# bot_schem_rev9.net
KiCad netlist of a schematic drawn in Altium Designer
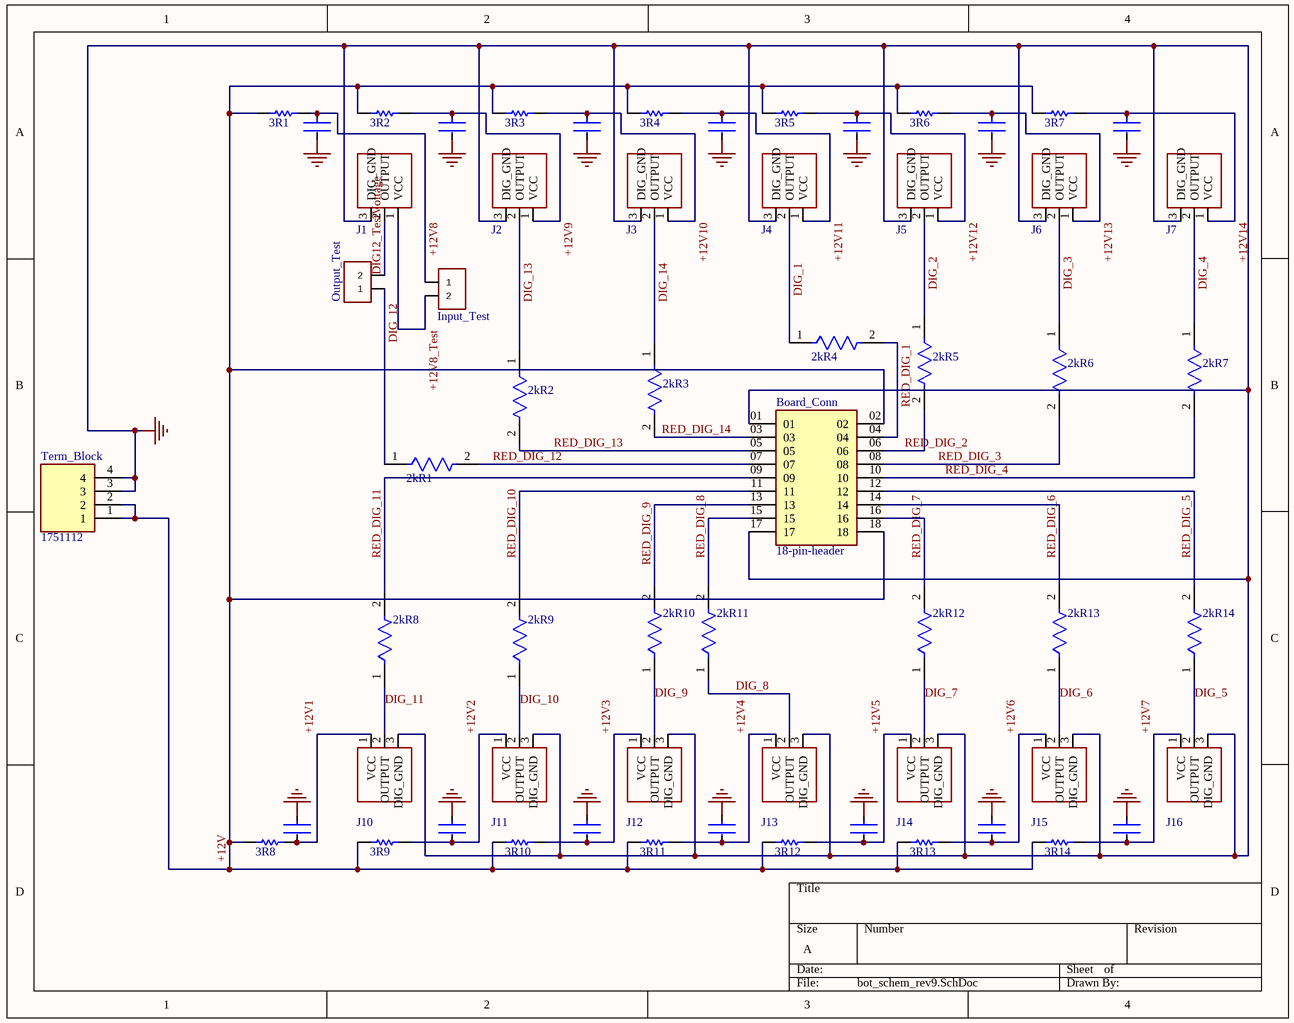
[diagram p0: bot_schem_rev9.SchDoc]

(export (version "E")
  (design (tool "Eeschema 10.0.6"))
  (components
    (comp (ref "2kR1")
      (value "CRCW06031K80FKEA")
      (footprint "2kOhm")
      (description "Res Thick Film 0603 1.8K Ohm 1% 1/10W ±100ppm/°C Molded SMD Paper T/R")
      (fields (field (name "MANUFACTURER") "Vishay") (field (name "TOLERANCE") "1%"))
      (libsource (lib "ps_schlib") (part "CRCW06031K80FKEA"))
    )
    (comp (ref "2kR2")
      (value "CRCW06031K80FKEA")
      (footprint "2kOhm")
      (description "Res Thick Film 0603 1.8K Ohm 1% 1/10W ±100ppm/°C Molded SMD Paper T/R")
      (fields (field (name "MANUFACTURER") "Vishay") (field (name "TOLERANCE") "1%"))
      (libsource (lib "ps_schlib") (part "CRCW06031K80FKEA"))
    )
    (comp (ref "2kR3")
      (value "CRCW06031K80FKEA")
      (footprint "2kOhm")
      (description "Res Thick Film 0603 1.8K Ohm 1% 1/10W ±100ppm/°C Molded SMD Paper T/R")
      (fields (field (name "MANUFACTURER") "Vishay") (field (name "TOLERANCE") "1%"))
      (libsource (lib "ps_schlib") (part "CRCW06031K80FKEA"))
    )
    (comp (ref "2kR4")
      (value "CRCW06031K80FKEA")
      (footprint "2kOhm")
      (description "Res Thick Film 0603 1.8K Ohm 1% 1/10W ±100ppm/°C Molded SMD Paper T/R")
      (fields (field (name "MANUFACTURER") "Vishay") (field (name "TOLERANCE") "1%"))
      (libsource (lib "ps_schlib") (part "CRCW06031K80FKEA"))
    )
    (comp (ref "2kR5")
      (value "CRCW06031K80FKEA")
      (footprint "2kOhm")
      (description "Res Thick Film 0603 1.8K Ohm 1% 1/10W ±100ppm/°C Molded SMD Paper T/R")
      (fields (field (name "MANUFACTURER") "Vishay") (field (name "TOLERANCE") "1%"))
      (libsource (lib "ps_schlib") (part "CRCW06031K80FKEA"))
    )
    (comp (ref "2kR6")
      (value "CRCW06031K80FKEA")
      (footprint "2kOhm")
      (description "Res Thick Film 0603 1.8K Ohm 1% 1/10W ±100ppm/°C Molded SMD Paper T/R")
      (fields (field (name "MANUFACTURER") "Vishay") (field (name "TOLERANCE") "1%"))
      (libsource (lib "ps_schlib") (part "CRCW06031K80FKEA"))
    )
    (comp (ref "2kR7")
      (value "CRCW06031K80FKEA")
      (footprint "2kOhm")
      (description "Res Thick Film 0603 1.8K Ohm 1% 1/10W ±100ppm/°C Molded SMD Paper T/R")
      (fields (field (name "MANUFACTURER") "Vishay") (field (name "TOLERANCE") "1%"))
      (libsource (lib "ps_schlib") (part "CRCW06031K80FKEA"))
    )
    (comp (ref "2kR8")
      (value "CRCW06031K80FKEA")
      (footprint "2kOhm")
      (description "Res Thick Film 0603 1.8K Ohm 1% 1/10W ±100ppm/°C Molded SMD Paper T/R")
      (fields (field (name "MANUFACTURER") "Vishay") (field (name "TOLERANCE") "1%"))
      (libsource (lib "ps_schlib") (part "CRCW06031K80FKEA"))
    )
    (comp (ref "2kR9")
      (value "CRCW06031K80FKEA")
      (footprint "2kOhm")
      (description "Res Thick Film 0603 1.8K Ohm 1% 1/10W ±100ppm/°C Molded SMD Paper T/R")
      (fields (field (name "MANUFACTURER") "Vishay") (field (name "TOLERANCE") "1%"))
      (libsource (lib "ps_schlib") (part "CRCW06031K80FKEA"))
    )
    (comp (ref "2kR10")
      (value "CRCW06031K80FKEA")
      (footprint "2kOhm")
      (description "Res Thick Film 0603 1.8K Ohm 1% 1/10W ±100ppm/°C Molded SMD Paper T/R")
      (fields (field (name "MANUFACTURER") "Vishay") (field (name "TOLERANCE") "1%"))
      (libsource (lib "ps_schlib") (part "CRCW06031K80FKEA"))
    )
    (comp (ref "2kR11")
      (value "CRCW06031K80FKEA")
      (footprint "2kOhm")
      (description "Res Thick Film 0603 1.8K Ohm 1% 1/10W ±100ppm/°C Molded SMD Paper T/R")
      (fields (field (name "MANUFACTURER") "Vishay") (field (name "TOLERANCE") "1%"))
      (libsource (lib "ps_schlib") (part "CRCW06031K80FKEA"))
    )
    (comp (ref "2kR12")
      (value "CRCW06031K80FKEA")
      (footprint "2kOhm")
      (description "Res Thick Film 0603 1.8K Ohm 1% 1/10W ±100ppm/°C Molded SMD Paper T/R")
      (fields (field (name "MANUFACTURER") "Vishay") (field (name "TOLERANCE") "1%"))
      (libsource (lib "ps_schlib") (part "CRCW06031K80FKEA"))
    )
    (comp (ref "2kR13")
      (value "CRCW06031K80FKEA")
      (footprint "2kOhm")
      (description "Res Thick Film 0603 1.8K Ohm 1% 1/10W ±100ppm/°C Molded SMD Paper T/R")
      (fields (field (name "MANUFACTURER") "Vishay") (field (name "TOLERANCE") "1%"))
      (libsource (lib "ps_schlib") (part "CRCW06031K80FKEA"))
    )
    (comp (ref "2kR14")
      (value "CRCW06031K80FKEA")
      (footprint "2kOhm")
      (description "Res Thick Film 0603 1.8K Ohm 1% 1/10W ±100ppm/°C Molded SMD Paper T/R")
      (fields (field (name "MANUFACTURER") "Vishay") (field (name "TOLERANCE") "1%"))
      (libsource (lib "ps_schlib") (part "CRCW06031K80FKEA"))
    )
    (comp (ref "3R1")
      (value "ERJ-2BQJR30X")
      (footprint "03 Ohm")
      (description "RES 0.3 OHM 5% 1/6W 0402")
      (fields (field (name "MANUFACTURER") "Panasonic") (field (name "TOLERANCE") "5%"))
      (libsource (lib "ps_schlib") (part "ERJ-2BQJR30X"))
    )
    (comp (ref "3R2")
      (value "ERJ-2BQJR30X")
      (footprint "03 Ohm")
      (description "RES 0.3 OHM 5% 1/6W 0402")
      (fields (field (name "MANUFACTURER") "Panasonic") (field (name "TOLERANCE") "5%"))
      (libsource (lib "ps_schlib") (part "ERJ-2BQJR30X"))
    )
    (comp (ref "3R3")
      (value "ERJ-2BQJR30X")
      (footprint "03 Ohm")
      (description "RES 0.3 OHM 5% 1/6W 0402")
      (fields (field (name "MANUFACTURER") "Panasonic") (field (name "TOLERANCE") "5%"))
      (libsource (lib "ps_schlib") (part "ERJ-2BQJR30X"))
    )
    (comp (ref "3R4")
      (value "ERJ-2BQJR30X")
      (footprint "03 Ohm")
      (description "RES 0.3 OHM 5% 1/6W 0402")
      (fields (field (name "MANUFACTURER") "Panasonic") (field (name "TOLERANCE") "5%"))
      (libsource (lib "ps_schlib") (part "ERJ-2BQJR30X"))
    )
    (comp (ref "3R5")
      (value "ERJ-2BQJR30X")
      (footprint "03 Ohm")
      (description "RES 0.3 OHM 5% 1/6W 0402")
      (fields (field (name "MANUFACTURER") "Panasonic") (field (name "TOLERANCE") "5%"))
      (libsource (lib "ps_schlib") (part "ERJ-2BQJR30X"))
    )
    (comp (ref "3R6")
      (value "ERJ-2BQJR30X")
      (footprint "03 Ohm")
      (description "RES 0.3 OHM 5% 1/6W 0402")
      (fields (field (name "MANUFACTURER") "Panasonic") (field (name "TOLERANCE") "5%"))
      (libsource (lib "ps_schlib") (part "ERJ-2BQJR30X"))
    )
    (comp (ref "3R7")
      (value "ERJ-2BQJR30X")
      (footprint "03 Ohm")
      (description "RES 0.3 OHM 5% 1/6W 0402")
      (fields (field (name "MANUFACTURER") "Panasonic") (field (name "TOLERANCE") "5%"))
      (libsource (lib "ps_schlib") (part "ERJ-2BQJR30X"))
    )
    (comp (ref "3R8")
      (value "ERJ-2BQJR30X")
      (footprint "03 Ohm")
      (description "RES 0.3 OHM 5% 1/6W 0402")
      (fields (field (name "MANUFACTURER") "Panasonic") (field (name "TOLERANCE") "5%"))
      (libsource (lib "ps_schlib") (part "ERJ-2BQJR30X"))
    )
    (comp (ref "3R9")
      (value "ERJ-2BQJR30X")
      (footprint "03 Ohm")
      (description "RES 0.3 OHM 5% 1/6W 0402")
      (fields (field (name "MANUFACTURER") "Panasonic") (field (name "TOLERANCE") "5%"))
      (libsource (lib "ps_schlib") (part "ERJ-2BQJR30X"))
    )
    (comp (ref "3R10")
      (value "ERJ-2BQJR30X")
      (footprint "03 Ohm")
      (description "RES 0.3 OHM 5% 1/6W 0402")
      (fields (field (name "MANUFACTURER") "Panasonic") (field (name "TOLERANCE") "5%"))
      (libsource (lib "ps_schlib") (part "ERJ-2BQJR30X"))
    )
    (comp (ref "3R11")
      (value "ERJ-2BQJR30X")
      (footprint "03 Ohm")
      (description "RES 0.3 OHM 5% 1/6W 0402")
      (fields (field (name "MANUFACTURER") "Panasonic") (field (name "TOLERANCE") "5%"))
      (libsource (lib "ps_schlib") (part "ERJ-2BQJR30X"))
    )
    (comp (ref "3R12")
      (value "ERJ-2BQJR30X")
      (footprint "03 Ohm")
      (description "RES 0.3 OHM 5% 1/6W 0402")
      (fields (field (name "MANUFACTURER") "Panasonic") (field (name "TOLERANCE") "5%"))
      (libsource (lib "ps_schlib") (part "ERJ-2BQJR30X"))
    )
    (comp (ref "3R13")
      (value "ERJ-2BQJR30X")
      (footprint "03 Ohm")
      (description "RES 0.3 OHM 5% 1/6W 0402")
      (fields (field (name "MANUFACTURER") "Panasonic") (field (name "TOLERANCE") "5%"))
      (libsource (lib "ps_schlib") (part "ERJ-2BQJR30X"))
    )
    (comp (ref "3R14")
      (value "ERJ-2BQJR30X")
      (footprint "03 Ohm")
      (description "RES 0.3 OHM 5% 1/6W 0402")
      (fields (field (name "MANUFACTURER") "Panasonic") (field (name "TOLERANCE") "5%"))
      (libsource (lib "ps_schlib") (part "ERJ-2BQJR30X"))
    )
    (comp (ref "Board_Conn")
      (value "18-pin-header")
      (footprint "18 pin header")
      (libsource (lib "bot_schlib") (part "18-pin-header"))
    )
    (comp (ref "C1")
      (value "C0805C104K5RACTU")
      (footprint "100nF")
      (description "Cap Ceramic 0.1uF 50V X7R 10% SMD 2.0 x 1.2 mm 125 C Paper T/R")
      (fields (field (name "MANUFACTURER") "KEMET") (field (name "TOLERANCE") "10%"))
      (libsource (lib "ps_schlib") (part "C0805C104K5RACTU"))
    )
    (comp (ref "C2")
      (value "C0805C104K5RACTU")
      (footprint "100nF")
      (description "Cap Ceramic 0.1uF 50V X7R 10% SMD 2.0 x 1.2 mm 125 C Paper T/R")
      (fields (field (name "MANUFACTURER") "KEMET") (field (name "TOLERANCE") "10%"))
      (libsource (lib "ps_schlib") (part "C0805C104K5RACTU"))
    )
    (comp (ref "C3")
      (value "C0805C104K5RACTU")
      (footprint "100nF")
      (description "Cap Ceramic 0.1uF 50V X7R 10% SMD 2.0 x 1.2 mm 125 C Paper T/R")
      (fields (field (name "MANUFACTURER") "KEMET") (field (name "TOLERANCE") "10%"))
      (libsource (lib "ps_schlib") (part "C0805C104K5RACTU"))
    )
    (comp (ref "C4")
      (value "C0805C104K5RACTU")
      (footprint "100nF")
      (description "Cap Ceramic 0.1uF 50V X7R 10% SMD 2.0 x 1.2 mm 125 C Paper T/R")
      (fields (field (name "MANUFACTURER") "KEMET") (field (name "TOLERANCE") "10%"))
      (libsource (lib "ps_schlib") (part "C0805C104K5RACTU"))
    )
    (comp (ref "C5")
      (value "C0805C104K5RACTU")
      (footprint "100nF")
      (description "Cap Ceramic 0.1uF 50V X7R 10% SMD 2.0 x 1.2 mm 125 C Paper T/R")
      (fields (field (name "MANUFACTURER") "KEMET") (field (name "TOLERANCE") "10%"))
      (libsource (lib "ps_schlib") (part "C0805C104K5RACTU"))
    )
    (comp (ref "C6")
      (value "C0805C104K5RACTU")
      (footprint "100nF")
      (description "Cap Ceramic 0.1uF 50V X7R 10% SMD 2.0 x 1.2 mm 125 C Paper T/R")
      (fields (field (name "MANUFACTURER") "KEMET") (field (name "TOLERANCE") "10%"))
      (libsource (lib "ps_schlib") (part "C0805C104K5RACTU"))
    )
    (comp (ref "C7")
      (value "C0805C104K5RACTU")
      (footprint "100nF")
      (description "Cap Ceramic 0.1uF 50V X7R 10% SMD 2.0 x 1.2 mm 125 C Paper T/R")
      (fields (field (name "MANUFACTURER") "KEMET") (field (name "TOLERANCE") "10%"))
      (libsource (lib "ps_schlib") (part "C0805C104K5RACTU"))
    )
    (comp (ref "C8")
      (value "C0805C104K5RACTU")
      (footprint "100nF")
      (description "Cap Ceramic 0.1uF 50V X7R 10% SMD 2.0 x 1.2 mm 125 C Paper T/R")
      (fields (field (name "MANUFACTURER") "KEMET") (field (name "TOLERANCE") "10%"))
      (libsource (lib "ps_schlib") (part "C0805C104K5RACTU"))
    )
    (comp (ref "C9")
      (value "C0805C104K5RACTU")
      (footprint "100nF")
      (description "Cap Ceramic 0.1uF 50V X7R 10% SMD 2.0 x 1.2 mm 125 C Paper T/R")
      (fields (field (name "MANUFACTURER") "KEMET") (field (name "TOLERANCE") "10%"))
      (libsource (lib "ps_schlib") (part "C0805C104K5RACTU"))
    )
    (comp (ref "C10")
      (value "C0805C104K5RACTU")
      (footprint "100nF")
      (description "Cap Ceramic 0.1uF 50V X7R 10% SMD 2.0 x 1.2 mm 125 C Paper T/R")
      (fields (field (name "MANUFACTURER") "KEMET") (field (name "TOLERANCE") "10%"))
      (libsource (lib "ps_schlib") (part "C0805C104K5RACTU"))
    )
    (comp (ref "C11")
      (value "C0805C104K5RACTU")
      (footprint "100nF")
      (description "Cap Ceramic 0.1uF 50V X7R 10% SMD 2.0 x 1.2 mm 125 C Paper T/R")
      (fields (field (name "MANUFACTURER") "KEMET") (field (name "TOLERANCE") "10%"))
      (libsource (lib "ps_schlib") (part "C0805C104K5RACTU"))
    )
    (comp (ref "C12")
      (value "C0805C104K5RACTU")
      (footprint "100nF")
      (description "Cap Ceramic 0.1uF 50V X7R 10% SMD 2.0 x 1.2 mm 125 C Paper T/R")
      (fields (field (name "MANUFACTURER") "KEMET") (field (name "TOLERANCE") "10%"))
      (libsource (lib "ps_schlib") (part "C0805C104K5RACTU"))
    )
    (comp (ref "C13")
      (value "C0805C104K5RACTU")
      (footprint "100nF")
      (description "Cap Ceramic 0.1uF 50V X7R 10% SMD 2.0 x 1.2 mm 125 C Paper T/R")
      (fields (field (name "MANUFACTURER") "KEMET") (field (name "TOLERANCE") "10%"))
      (libsource (lib "ps_schlib") (part "C0805C104K5RACTU"))
    )
    (comp (ref "C14")
      (value "C0805C104K5RACTU")
      (footprint "100nF")
      (description "Cap Ceramic 0.1uF 50V X7R 10% SMD 2.0 x 1.2 mm 125 C Paper T/R")
      (fields (field (name "MANUFACTURER") "KEMET") (field (name "TOLERANCE") "10%"))
      (libsource (lib "ps_schlib") (part "C0805C104K5RACTU"))
    )
    (comp (ref "Input_Test")
      (value "PRPC001DFAN-RC")
      (footprint "PRPC001DFAN-RC")
      (description "Conn Header Vert 2POS")
      (fields (field (name "MANUFACTURER") "Sullins"))
      (libsource (lib "ps_schlib") (part "PRPC001DFAN-RC"))
    )
    (comp (ref "J1")
      (value "IF-D95T")
      (footprint "IF-D95")
      (description "DETECTOR PHOTOLOGIC TTL/CMOS")
      (fields (field (name "MANUFACTURER") "Industrial Fiber Optics"))
      (libsource (lib "ps_schlib") (part "IF-D95T"))
    )
    (comp (ref "J2")
      (value "IF-D95T")
      (footprint "IF-D95")
      (description "DETECTOR PHOTOLOGIC TTL/CMOS")
      (fields (field (name "MANUFACTURER") "Industrial Fiber Optics"))
      (libsource (lib "ps_schlib") (part "IF-D95T"))
    )
    (comp (ref "J3")
      (value "IF-D95T")
      (footprint "IF-D95")
      (description "DETECTOR PHOTOLOGIC TTL/CMOS")
      (fields (field (name "MANUFACTURER") "Industrial Fiber Optics"))
      (libsource (lib "ps_schlib") (part "IF-D95T"))
    )
    (comp (ref "J4")
      (value "IF-D95T")
      (footprint "IF-D95")
      (description "DETECTOR PHOTOLOGIC TTL/CMOS")
      (fields (field (name "MANUFACTURER") "Industrial Fiber Optics"))
      (libsource (lib "ps_schlib") (part "IF-D95T"))
    )
    (comp (ref "J5")
      (value "IF-D95T")
      (footprint "IF-D95")
      (description "DETECTOR PHOTOLOGIC TTL/CMOS")
      (fields (field (name "MANUFACTURER") "Industrial Fiber Optics"))
      (libsource (lib "ps_schlib") (part "IF-D95T"))
    )
    (comp (ref "J6")
      (value "IF-D95T")
      (footprint "IF-D95")
      (description "DETECTOR PHOTOLOGIC TTL/CMOS")
      (fields (field (name "MANUFACTURER") "Industrial Fiber Optics"))
      (libsource (lib "ps_schlib") (part "IF-D95T"))
    )
    (comp (ref "J7")
      (value "IF-D95T")
      (footprint "IF-D95")
      (description "DETECTOR PHOTOLOGIC TTL/CMOS")
      (fields (field (name "MANUFACTURER") "Industrial Fiber Optics"))
      (libsource (lib "ps_schlib") (part "IF-D95T"))
    )
    (comp (ref "J10")
      (value "IF-D95T")
      (footprint "IF-D95")
      (description "DETECTOR PHOTOLOGIC TTL/CMOS")
      (fields (field (name "MANUFACTURER") "Industrial Fiber Optics"))
      (libsource (lib "ps_schlib") (part "IF-D95T"))
    )
    (comp (ref "J11")
      (value "IF-D95T")
      (footprint "IF-D95")
      (description "DETECTOR PHOTOLOGIC TTL/CMOS")
      (fields (field (name "MANUFACTURER") "Industrial Fiber Optics"))
      (libsource (lib "ps_schlib") (part "IF-D95T"))
    )
    (comp (ref "J12")
      (value "IF-D95T")
      (footprint "IF-D95")
      (description "DETECTOR PHOTOLOGIC TTL/CMOS")
      (fields (field (name "MANUFACTURER") "Industrial Fiber Optics"))
      (libsource (lib "ps_schlib") (part "IF-D95T"))
    )
    (comp (ref "J13")
      (value "IF-D95T")
      (footprint "IF-D95")
      (description "DETECTOR PHOTOLOGIC TTL/CMOS")
      (fields (field (name "MANUFACTURER") "Industrial Fiber Optics"))
      (libsource (lib "ps_schlib") (part "IF-D95T"))
    )
    (comp (ref "J14")
      (value "IF-D95T")
      (footprint "IF-D95")
      (description "DETECTOR PHOTOLOGIC TTL/CMOS")
      (fields (field (name "MANUFACTURER") "Industrial Fiber Optics"))
      (libsource (lib "ps_schlib") (part "IF-D95T"))
    )
    (comp (ref "J15")
      (value "IF-D95T")
      (footprint "IF-D95")
      (description "DETECTOR PHOTOLOGIC TTL/CMOS")
      (fields (field (name "MANUFACTURER") "Industrial Fiber Optics"))
      (libsource (lib "ps_schlib") (part "IF-D95T"))
    )
    (comp (ref "J16")
      (value "IF-D95T")
      (footprint "IF-D95")
      (description "DETECTOR PHOTOLOGIC TTL/CMOS")
      (fields (field (name "MANUFACTURER") "Industrial Fiber Optics"))
      (libsource (lib "ps_schlib") (part "IF-D95T"))
    )
    (comp (ref "Output_Test")
      (value "PRPC001DFAN-RC")
      (footprint "PRPC001DFAN-RC")
      (description "Conn Header Vert 2POS")
      (fields (field (name "MANUFACTURER") "Sullins"))
      (libsource (lib "ps_schlib") (part "PRPC001DFAN-RC"))
    )
    (comp (ref "Term_Block")
      (value "1751112")
      (footprint "SamacSys:1751112")
      (description "Connector")
      (libsource (lib "*") (part "1751112"))
    )
  )
  (nets
    (net (code "1") (name "/+12V") (class "Default")
      (node (ref "3R1") (pin "1") (pinfunction "1_1") (pintype "passive"))
      (node (ref "3R10") (pin "1") (pinfunction "1_1") (pintype "passive"))
      (node (ref "3R11") (pin "1") (pinfunction "1_1") (pintype "passive"))
      (node (ref "3R12") (pin "1") (pinfunction "1_1") (pintype "passive"))
      (node (ref "3R13") (pin "1") (pinfunction "1_1") (pintype "passive"))
      (node (ref "3R14") (pin "1") (pinfunction "1_1") (pintype "passive"))
      (node (ref "3R2") (pin "1") (pinfunction "1_1") (pintype "passive"))
      (node (ref "3R3") (pin "1") (pinfunction "1_1") (pintype "passive"))
      (node (ref "3R4") (pin "1") (pinfunction "1_1") (pintype "passive"))
      (node (ref "3R5") (pin "1") (pinfunction "1_1") (pintype "passive"))
      (node (ref "3R6") (pin "1") (pinfunction "1_1") (pintype "passive"))
      (node (ref "3R7") (pin "1") (pinfunction "1_1") (pintype "passive"))
      (node (ref "3R8") (pin "1") (pinfunction "1_1") (pintype "passive"))
      (node (ref "3R9") (pin "1") (pinfunction "1_1") (pintype "passive"))
      (node (ref "Board_Conn") (pin "02") (pinfunction "02_02") (pintype "passive"))
      (node (ref "Board_Conn") (pin "18") (pinfunction "18_18") (pintype "passive"))
      (node (ref "Term_Block") (pin "1") (pinfunction "1_1") (pintype "passive"))
      (node (ref "Term_Block") (pin "2") (pinfunction "2_2") (pintype "passive"))
    )
    (net (code "2") (name "/+12V1") (class "Default")
      (node (ref "3R8") (pin "2") (pinfunction "2_2") (pintype "passive"))
      (node (ref "C8") (pin "2") (pinfunction "2_2") (pintype "passive"))
      (node (ref "J10") (pin "1") (pinfunction "VCC_1") (pintype "passive"))
    )
    (net (code "3") (name "/+12V2") (class "Default")
      (node (ref "3R9") (pin "2") (pinfunction "2_2") (pintype "passive"))
      (node (ref "C9") (pin "2") (pinfunction "2_2") (pintype "passive"))
      (node (ref "J11") (pin "1") (pinfunction "VCC_1") (pintype "passive"))
    )
    (net (code "4") (name "/+12V3") (class "Default")
      (node (ref "3R10") (pin "2") (pinfunction "2_2") (pintype "passive"))
      (node (ref "C10") (pin "2") (pinfunction "2_2") (pintype "passive"))
      (node (ref "J12") (pin "1") (pinfunction "VCC_1") (pintype "passive"))
    )
    (net (code "5") (name "/+12V4") (class "Default")
      (node (ref "3R11") (pin "2") (pinfunction "2_2") (pintype "passive"))
      (node (ref "C11") (pin "2") (pinfunction "2_2") (pintype "passive"))
      (node (ref "J13") (pin "1") (pinfunction "VCC_1") (pintype "passive"))
    )
    (net (code "6") (name "/+12V5") (class "Default")
      (node (ref "3R12") (pin "2") (pinfunction "2_2") (pintype "passive"))
      (node (ref "C12") (pin "2") (pinfunction "2_2") (pintype "passive"))
      (node (ref "J14") (pin "1") (pinfunction "VCC_1") (pintype "passive"))
    )
    (net (code "7") (name "/+12V6") (class "Default")
      (node (ref "3R13") (pin "2") (pinfunction "2_2") (pintype "passive"))
      (node (ref "C13") (pin "2") (pinfunction "2_2") (pintype "passive"))
      (node (ref "J15") (pin "1") (pinfunction "VCC_1") (pintype "passive"))
    )
    (net (code "8") (name "/+12V7") (class "Default")
      (node (ref "3R14") (pin "2") (pinfunction "2_2") (pintype "passive"))
      (node (ref "C14") (pin "2") (pinfunction "2_2") (pintype "passive"))
      (node (ref "J16") (pin "1") (pinfunction "VCC_1") (pintype "passive"))
    )
    (net (code "9") (name "/+12V8") (class "Default")
      (node (ref "3R1") (pin "2") (pinfunction "2_2") (pintype "passive"))
      (node (ref "C1") (pin "1") (pinfunction "1_1") (pintype "passive"))
      (node (ref "Input_Test") (pin "1") (pinfunction "1_1") (pintype "passive"))
    )
    (net (code "10") (name "/+12V8_Test") (class "Default")
      (node (ref "Input_Test") (pin "2") (pinfunction "2_2") (pintype "passive"))
      (node (ref "J1") (pin "1") (pinfunction "VCC_1") (pintype "passive"))
    )
    (net (code "11") (name "/+12V9") (class "Default")
      (node (ref "3R2") (pin "2") (pinfunction "2_2") (pintype "passive"))
      (node (ref "C2") (pin "1") (pinfunction "1_1") (pintype "passive"))
      (node (ref "J2") (pin "1") (pinfunction "VCC_1") (pintype "passive"))
    )
    (net (code "12") (name "/+12V10") (class "Default")
      (node (ref "3R3") (pin "2") (pinfunction "2_2") (pintype "passive"))
      (node (ref "C3") (pin "1") (pinfunction "1_1") (pintype "passive"))
      (node (ref "J3") (pin "1") (pinfunction "VCC_1") (pintype "passive"))
    )
    (net (code "13") (name "/+12V11") (class "Default")
      (node (ref "3R4") (pin "2") (pinfunction "2_2") (pintype "passive"))
      (node (ref "C4") (pin "1") (pinfunction "1_1") (pintype "passive"))
      (node (ref "J4") (pin "1") (pinfunction "VCC_1") (pintype "passive"))
    )
    (net (code "14") (name "/+12V12") (class "Default")
      (node (ref "3R5") (pin "2") (pinfunction "2_2") (pintype "passive"))
      (node (ref "C5") (pin "1") (pinfunction "1_1") (pintype "passive"))
      (node (ref "J5") (pin "1") (pinfunction "VCC_1") (pintype "passive"))
    )
    (net (code "15") (name "/+12V13") (class "Default")
      (node (ref "3R6") (pin "2") (pinfunction "2_2") (pintype "passive"))
      (node (ref "C6") (pin "1") (pinfunction "1_1") (pintype "passive"))
      (node (ref "J6") (pin "1") (pinfunction "VCC_1") (pintype "passive"))
    )
    (net (code "16") (name "/+12V14") (class "Default")
      (node (ref "3R7") (pin "2") (pinfunction "2_2") (pintype "passive"))
      (node (ref "C7") (pin "1") (pinfunction "1_1") (pintype "passive"))
      (node (ref "J7") (pin "1") (pinfunction "VCC_1") (pintype "passive"))
    )
    (net (code "18") (name "/DIG12_TestVoltage") (class "Default")
      (node (ref "J1") (pin "2") (pinfunction "OUTPUT_2") (pintype "passive"))
      (node (ref "Output_Test") (pin "2") (pinfunction "2_2") (pintype "passive"))
    )
    (net (code "19") (name "/DIG_1") (class "Default")
      (node (ref "2kR4") (pin "1") (pinfunction "1_1") (pintype "passive"))
      (node (ref "J4") (pin "2") (pinfunction "OUTPUT_2") (pintype "passive"))
    )
    (net (code "20") (name "/DIG_2") (class "Default")
      (node (ref "2kR5") (pin "1") (pinfunction "1_1") (pintype "passive"))
      (node (ref "J5") (pin "2") (pinfunction "OUTPUT_2") (pintype "passive"))
    )
    (net (code "21") (name "/DIG_3") (class "Default")
      (node (ref "2kR6") (pin "1") (pinfunction "1_1") (pintype "passive"))
      (node (ref "J6") (pin "2") (pinfunction "OUTPUT_2") (pintype "passive"))
    )
    (net (code "22") (name "/DIG_4") (class "Default")
      (node (ref "2kR7") (pin "1") (pinfunction "1_1") (pintype "passive"))
      (node (ref "J7") (pin "2") (pinfunction "OUTPUT_2") (pintype "passive"))
    )
    (net (code "23") (name "/DIG_5") (class "Default")
      (node (ref "2kR14") (pin "1") (pinfunction "1_1") (pintype "passive"))
      (node (ref "J16") (pin "2") (pinfunction "OUTPUT_2") (pintype "passive"))
    )
    (net (code "24") (name "/DIG_6") (class "Default")
      (node (ref "2kR13") (pin "1") (pinfunction "1_1") (pintype "passive"))
      (node (ref "J15") (pin "2") (pinfunction "OUTPUT_2") (pintype "passive"))
    )
    (net (code "25") (name "/DIG_7") (class "Default")
      (node (ref "2kR12") (pin "1") (pinfunction "1_1") (pintype "passive"))
      (node (ref "J14") (pin "2") (pinfunction "OUTPUT_2") (pintype "passive"))
    )
    (net (code "26") (name "/DIG_8") (class "Default")
      (node (ref "2kR11") (pin "1") (pinfunction "1_1") (pintype "passive"))
      (node (ref "J13") (pin "2") (pinfunction "OUTPUT_2") (pintype "passive"))
    )
    (net (code "27") (name "/DIG_9") (class "Default")
      (node (ref "2kR10") (pin "1") (pinfunction "1_1") (pintype "passive"))
      (node (ref "J12") (pin "2") (pinfunction "OUTPUT_2") (pintype "passive"))
    )
    (net (code "28") (name "/DIG_10") (class "Default")
      (node (ref "2kR9") (pin "1") (pinfunction "1_1") (pintype "passive"))
      (node (ref "J11") (pin "2") (pinfunction "OUTPUT_2") (pintype "passive"))
    )
    (net (code "29") (name "/DIG_11") (class "Default")
      (node (ref "2kR8") (pin "1") (pinfunction "1_1") (pintype "passive"))
      (node (ref "J10") (pin "2") (pinfunction "OUTPUT_2") (pintype "passive"))
    )
    (net (code "30") (name "/DIG_12") (class "Default")
      (node (ref "2kR1") (pin "1") (pinfunction "1_1") (pintype "passive"))
      (node (ref "Output_Test") (pin "1") (pinfunction "1_1") (pintype "passive"))
    )
    (net (code "31") (name "/DIG_13") (class "Default")
      (node (ref "2kR2") (pin "1") (pinfunction "1_1") (pintype "passive"))
      (node (ref "J2") (pin "2") (pinfunction "OUTPUT_2") (pintype "passive"))
    )
    (net (code "32") (name "/DIG_14") (class "Default")
      (node (ref "2kR3") (pin "1") (pinfunction "1_1") (pintype "passive"))
      (node (ref "J3") (pin "2") (pinfunction "OUTPUT_2") (pintype "passive"))
    )
    (net (code "33") (name "/RED_DIG_1") (class "Default")
      (node (ref "2kR4") (pin "2") (pinfunction "2_2") (pintype "passive"))
      (node (ref "Board_Conn") (pin "04") (pinfunction "04_04") (pintype "passive"))
    )
    (net (code "34") (name "/RED_DIG_2") (class "Default")
      (node (ref "2kR5") (pin "2") (pinfunction "2_2") (pintype "passive"))
      (node (ref "Board_Conn") (pin "06") (pinfunction "06_06") (pintype "passive"))
    )
    (net (code "35") (name "/RED_DIG_3") (class "Default")
      (node (ref "2kR6") (pin "2") (pinfunction "2_2") (pintype "passive"))
      (node (ref "Board_Conn") (pin "08") (pinfunction "08_08") (pintype "passive"))
    )
    (net (code "36") (name "/RED_DIG_4") (class "Default")
      (node (ref "2kR7") (pin "2") (pinfunction "2_2") (pintype "passive"))
      (node (ref "Board_Conn") (pin "10") (pinfunction "10_10") (pintype "passive"))
    )
    (net (code "37") (name "/RED_DIG_5") (class "Default")
      (node (ref "2kR14") (pin "2") (pinfunction "2_2") (pintype "passive"))
      (node (ref "Board_Conn") (pin "12") (pinfunction "12_12") (pintype "passive"))
    )
    (net (code "38") (name "/RED_DIG_6") (class "Default")
      (node (ref "2kR13") (pin "2") (pinfunction "2_2") (pintype "passive"))
      (node (ref "Board_Conn") (pin "14") (pinfunction "14_14") (pintype "passive"))
    )
    (net (code "39") (name "/RED_DIG_7") (class "Default")
      (node (ref "2kR12") (pin "2") (pinfunction "2_2") (pintype "passive"))
      (node (ref "Board_Conn") (pin "16") (pinfunction "16_16") (pintype "passive"))
    )
    (net (code "40") (name "/RED_DIG_8") (class "Default")
      (node (ref "2kR11") (pin "2") (pinfunction "2_2") (pintype "passive"))
      (node (ref "Board_Conn") (pin "15") (pinfunction "15_15") (pintype "passive"))
    )
    (net (code "41") (name "/RED_DIG_9") (class "Default")
      (node (ref "2kR10") (pin "2") (pinfunction "2_2") (pintype "passive"))
      (node (ref "Board_Conn") (pin "13") (pinfunction "13_13") (pintype "passive"))
    )
    (net (code "42") (name "/RED_DIG_10") (class "Default")
      (node (ref "2kR9") (pin "2") (pinfunction "2_2") (pintype "passive"))
      (node (ref "Board_Conn") (pin "11") (pinfunction "11_11") (pintype "passive"))
    )
    (net (code "43") (name "/RED_DIG_11") (class "Default")
      (node (ref "2kR8") (pin "2") (pinfunction "2_2") (pintype "passive"))
      (node (ref "Board_Conn") (pin "09") (pinfunction "09_09") (pintype "passive"))
    )
    (net (code "44") (name "/RED_DIG_12") (class "Default")
      (node (ref "2kR1") (pin "2") (pinfunction "2_2") (pintype "passive"))
      (node (ref "Board_Conn") (pin "07") (pinfunction "07_07") (pintype "passive"))
    )
    (net (code "45") (name "/RED_DIG_13") (class "Default")
      (node (ref "2kR2") (pin "2") (pinfunction "2_2") (pintype "passive"))
      (node (ref "Board_Conn") (pin "05") (pinfunction "05_05") (pintype "passive"))
    )
    (net (code "46") (name "/RED_DIG_14") (class "Default")
      (node (ref "2kR3") (pin "2") (pinfunction "2_2") (pintype "passive"))
      (node (ref "Board_Conn") (pin "03") (pinfunction "03_03") (pintype "passive"))
    )
    (net (code "47") (name "GND") (class "Default")
      (node (ref "Board_Conn") (pin "01") (pinfunction "01_01") (pintype "passive"))
      (node (ref "Board_Conn") (pin "17") (pinfunction "17_17") (pintype "passive"))
      (node (ref "C1") (pin "2") (pinfunction "2_2") (pintype "passive"))
      (node (ref "C10") (pin "1") (pinfunction "1_1") (pintype "passive"))
      (node (ref "C11") (pin "1") (pinfunction "1_1") (pintype "passive"))
      (node (ref "C12") (pin "1") (pinfunction "1_1") (pintype "passive"))
      (node (ref "C13") (pin "1") (pinfunction "1_1") (pintype "passive"))
      (node (ref "C14") (pin "1") (pinfunction "1_1") (pintype "passive"))
      (node (ref "C2") (pin "2") (pinfunction "2_2") (pintype "passive"))
      (node (ref "C3") (pin "2") (pinfunction "2_2") (pintype "passive"))
      (node (ref "C4") (pin "2") (pinfunction "2_2") (pintype "passive"))
      (node (ref "C5") (pin "2") (pinfunction "2_2") (pintype "passive"))
      (node (ref "C6") (pin "2") (pinfunction "2_2") (pintype "passive"))
      (node (ref "C7") (pin "2") (pinfunction "2_2") (pintype "passive"))
      (node (ref "C8") (pin "1") (pinfunction "1_1") (pintype "passive"))
      (node (ref "C9") (pin "1") (pinfunction "1_1") (pintype "passive"))
      (node (ref "J1") (pin "3") (pinfunction "DIG_GND_3") (pintype "passive"))
      (node (ref "J10") (pin "3") (pinfunction "DIG_GND_3") (pintype "passive"))
      (node (ref "J11") (pin "3") (pinfunction "DIG_GND_3") (pintype "passive"))
      (node (ref "J12") (pin "3") (pinfunction "DIG_GND_3") (pintype "passive"))
      (node (ref "J13") (pin "3") (pinfunction "DIG_GND_3") (pintype "passive"))
      (node (ref "J14") (pin "3") (pinfunction "DIG_GND_3") (pintype "passive"))
      (node (ref "J15") (pin "3") (pinfunction "DIG_GND_3") (pintype "passive"))
      (node (ref "J16") (pin "3") (pinfunction "DIG_GND_3") (pintype "passive"))
      (node (ref "J2") (pin "3") (pinfunction "DIG_GND_3") (pintype "passive"))
      (node (ref "J3") (pin "3") (pinfunction "DIG_GND_3") (pintype "passive"))
      (node (ref "J4") (pin "3") (pinfunction "DIG_GND_3") (pintype "passive"))
      (node (ref "J5") (pin "3") (pinfunction "DIG_GND_3") (pintype "passive"))
      (node (ref "J6") (pin "3") (pinfunction "DIG_GND_3") (pintype "passive"))
      (node (ref "J7") (pin "3") (pinfunction "DIG_GND_3") (pintype "passive"))
      (node (ref "Term_Block") (pin "3") (pinfunction "3_3") (pintype "passive"))
      (node (ref "Term_Block") (pin "4") (pinfunction "4_4") (pintype "passive"))
    )
  )
)
